# shiftReg.net
KiCad netlist of a schematic drawn in EAGLE
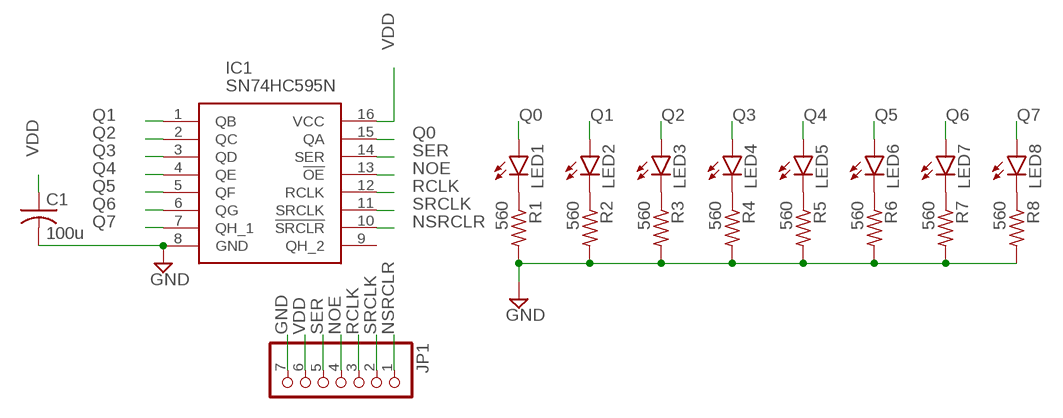
[diagram p0: schematic, sheet 1]

(export (version "E")
  (design (tool "Eeschema 10.0.6"))
  (components
    (comp (ref "C1")
      (value "100u")
      (footprint "eagle-import:C0805")
      (libsource (lib "eagle-import") (part "C-USC0805"))
    )
    (comp (ref "IC1")
      (value "SN74HC595N")
      (footprint "eagle-import:DIP794W53P254L1930H508Q16N")
      (fields (field (name "MOUSER_PART_NUMBER") "595-SN74HC595N"))
      (libsource (lib "eagle-import") (part "SN74HC595N"))
    )
    (comp (ref "JP1")
      (value "PINHD-1X7")
      (footprint "eagle-import:1X07")
      (libsource (lib "eagle-import") (part "PINHD-1X7"))
    )
    (comp (ref "LED1")
      (value "LEDCHIP-LED0805")
      (footprint "eagle-import:CHIP-LED0805")
      (libsource (lib "eagle-import") (part "LEDCHIP-LED0805"))
    )
    (comp (ref "LED2")
      (value "LEDCHIP-LED0805")
      (footprint "eagle-import:CHIP-LED0805")
      (libsource (lib "eagle-import") (part "LEDCHIP-LED0805"))
    )
    (comp (ref "LED3")
      (value "LEDCHIP-LED0805")
      (footprint "eagle-import:CHIP-LED0805")
      (libsource (lib "eagle-import") (part "LEDCHIP-LED0805"))
    )
    (comp (ref "LED4")
      (value "LEDCHIP-LED0805")
      (footprint "eagle-import:CHIP-LED0805")
      (libsource (lib "eagle-import") (part "LEDCHIP-LED0805"))
    )
    (comp (ref "LED5")
      (value "LEDCHIP-LED0805")
      (footprint "eagle-import:CHIP-LED0805")
      (libsource (lib "eagle-import") (part "LEDCHIP-LED0805"))
    )
    (comp (ref "LED6")
      (value "LEDCHIP-LED0805")
      (footprint "eagle-import:CHIP-LED0805")
      (libsource (lib "eagle-import") (part "LEDCHIP-LED0805"))
    )
    (comp (ref "LED7")
      (value "LEDCHIP-LED0805")
      (footprint "eagle-import:CHIP-LED0805")
      (libsource (lib "eagle-import") (part "LEDCHIP-LED0805"))
    )
    (comp (ref "LED8")
      (value "LEDCHIP-LED0805")
      (footprint "eagle-import:CHIP-LED0805")
      (libsource (lib "eagle-import") (part "LEDCHIP-LED0805"))
    )
    (comp (ref "R1")
      (value "560")
      (footprint "eagle-import:R0805")
      (libsource (lib "eagle-import") (part "R-US_R0805"))
    )
    (comp (ref "R2")
      (value "560")
      (footprint "eagle-import:R0805")
      (libsource (lib "eagle-import") (part "R-US_R0805"))
    )
    (comp (ref "R3")
      (value "560")
      (footprint "eagle-import:R0805")
      (libsource (lib "eagle-import") (part "R-US_R0805"))
    )
    (comp (ref "R4")
      (value "560")
      (footprint "eagle-import:R0805")
      (libsource (lib "eagle-import") (part "R-US_R0805"))
    )
    (comp (ref "R5")
      (value "560")
      (footprint "eagle-import:R0805")
      (libsource (lib "eagle-import") (part "R-US_R0805"))
    )
    (comp (ref "R6")
      (value "560")
      (footprint "eagle-import:R0805")
      (libsource (lib "eagle-import") (part "R-US_R0805"))
    )
    (comp (ref "R7")
      (value "560")
      (footprint "eagle-import:R0805")
      (libsource (lib "eagle-import") (part "R-US_R0805"))
    )
    (comp (ref "R8")
      (value "560")
      (footprint "eagle-import:R0805")
      (libsource (lib "eagle-import") (part "R-US_R0805"))
    )
  )
  (nets
    (net (code "1") (name "/NOE") (class "Default")
      (node (ref "IC1") (pin "13") (pinfunction "~{OE}_13") (pintype "bidirectional"))
      (node (ref "JP1") (pin "4") (pinfunction "4_4") (pintype "passive"))
    )
    (net (code "2") (name "/NSRCLR") (class "Default")
      (node (ref "IC1") (pin "10") (pinfunction "~{SRCLR}_10") (pintype "bidirectional"))
      (node (ref "JP1") (pin "1") (pinfunction "1_1") (pintype "passive"))
    )
    (net (code "3") (name "/Q0") (class "Default")
      (node (ref "IC1") (pin "15") (pinfunction "QA_15") (pintype "bidirectional"))
      (node (ref "LED1") (pin "A") (pinfunction "A_A") (pintype "passive"))
    )
    (net (code "4") (name "/Q1") (class "Default")
      (node (ref "IC1") (pin "1") (pinfunction "QB_1") (pintype "bidirectional"))
      (node (ref "LED2") (pin "A") (pinfunction "A_A") (pintype "passive"))
    )
    (net (code "5") (name "/Q2") (class "Default")
      (node (ref "IC1") (pin "2") (pinfunction "QC_2") (pintype "bidirectional"))
      (node (ref "LED3") (pin "A") (pinfunction "A_A") (pintype "passive"))
    )
    (net (code "6") (name "/Q3") (class "Default")
      (node (ref "IC1") (pin "3") (pinfunction "QD_3") (pintype "bidirectional"))
      (node (ref "LED4") (pin "A") (pinfunction "A_A") (pintype "passive"))
    )
    (net (code "7") (name "/Q4") (class "Default")
      (node (ref "IC1") (pin "4") (pinfunction "QE_4") (pintype "bidirectional"))
      (node (ref "LED5") (pin "A") (pinfunction "A_A") (pintype "passive"))
    )
    (net (code "8") (name "/Q5") (class "Default")
      (node (ref "IC1") (pin "5") (pinfunction "QF_5") (pintype "bidirectional"))
      (node (ref "LED6") (pin "A") (pinfunction "A_A") (pintype "passive"))
    )
    (net (code "9") (name "/Q6") (class "Default")
      (node (ref "IC1") (pin "6") (pinfunction "QG_6") (pintype "bidirectional"))
      (node (ref "LED7") (pin "A") (pinfunction "A_A") (pintype "passive"))
    )
    (net (code "10") (name "/Q7") (class "Default")
      (node (ref "IC1") (pin "7") (pinfunction "QH_1_7") (pintype "bidirectional"))
      (node (ref "LED8") (pin "A") (pinfunction "A_A") (pintype "passive"))
    )
    (net (code "11") (name "/RCLK") (class "Default")
      (node (ref "IC1") (pin "12") (pinfunction "RCLK_12") (pintype "input"))
      (node (ref "JP1") (pin "3") (pinfunction "3_3") (pintype "passive"))
    )
    (net (code "12") (name "/SER") (class "Default")
      (node (ref "IC1") (pin "14") (pinfunction "SER_14") (pintype "bidirectional"))
      (node (ref "JP1") (pin "5") (pinfunction "5_5") (pintype "passive"))
    )
    (net (code "13") (name "/SRCLK") (class "Default")
      (node (ref "IC1") (pin "11") (pinfunction "SRCLK_11") (pintype "input"))
      (node (ref "JP1") (pin "2") (pinfunction "2_2") (pintype "passive"))
    )
    (net (code "14") (name "/VDD") (class "Default")
      (node (ref "C1") (pin "1") (pinfunction "1_1") (pintype "passive"))
      (node (ref "IC1") (pin "16") (pinfunction "VCC_16") (pintype "power_in"))
      (node (ref "JP1") (pin "6") (pinfunction "6_6") (pintype "passive"))
    )
    (net (code "15") (name "GND") (class "Default")
      (node (ref "C1") (pin "2") (pinfunction "2_2") (pintype "passive"))
      (node (ref "IC1") (pin "8") (pinfunction "GND_8") (pintype "power_in"))
      (node (ref "JP1") (pin "7") (pinfunction "7_7") (pintype "passive"))
      (node (ref "R1") (pin "2") (pinfunction "2_2") (pintype "passive"))
      (node (ref "R2") (pin "2") (pinfunction "2_2") (pintype "passive"))
      (node (ref "R3") (pin "2") (pinfunction "2_2") (pintype "passive"))
      (node (ref "R4") (pin "2") (pinfunction "2_2") (pintype "passive"))
      (node (ref "R5") (pin "2") (pinfunction "2_2") (pintype "passive"))
      (node (ref "R6") (pin "2") (pinfunction "2_2") (pintype "passive"))
      (node (ref "R7") (pin "2") (pinfunction "2_2") (pintype "passive"))
      (node (ref "R8") (pin "2") (pinfunction "2_2") (pintype "passive"))
    )
    (net (code "16") (name "Net-(LED1-PadC)") (class "Default")
      (node (ref "LED1") (pin "C") (pinfunction "C_C") (pintype "passive"))
      (node (ref "R1") (pin "1") (pinfunction "1_1") (pintype "passive"))
    )
    (net (code "17") (name "Net-(LED2-PadC)") (class "Default")
      (node (ref "LED2") (pin "C") (pinfunction "C_C") (pintype "passive"))
      (node (ref "R2") (pin "1") (pinfunction "1_1") (pintype "passive"))
    )
    (net (code "18") (name "Net-(LED3-PadC)") (class "Default")
      (node (ref "LED3") (pin "C") (pinfunction "C_C") (pintype "passive"))
      (node (ref "R3") (pin "1") (pinfunction "1_1") (pintype "passive"))
    )
    (net (code "19") (name "Net-(LED4-PadC)") (class "Default")
      (node (ref "LED4") (pin "C") (pinfunction "C_C") (pintype "passive"))
      (node (ref "R4") (pin "1") (pinfunction "1_1") (pintype "passive"))
    )
    (net (code "20") (name "Net-(LED5-PadC)") (class "Default")
      (node (ref "LED5") (pin "C") (pinfunction "C_C") (pintype "passive"))
      (node (ref "R5") (pin "1") (pinfunction "1_1") (pintype "passive"))
    )
    (net (code "21") (name "Net-(LED6-PadC)") (class "Default")
      (node (ref "LED6") (pin "C") (pinfunction "C_C") (pintype "passive"))
      (node (ref "R6") (pin "1") (pinfunction "1_1") (pintype "passive"))
    )
    (net (code "22") (name "Net-(LED7-PadC)") (class "Default")
      (node (ref "LED7") (pin "C") (pinfunction "C_C") (pintype "passive"))
      (node (ref "R7") (pin "1") (pinfunction "1_1") (pintype "passive"))
    )
    (net (code "23") (name "Net-(LED8-PadC)") (class "Default")
      (node (ref "LED8") (pin "C") (pinfunction "C_C") (pintype "passive"))
      (node (ref "R8") (pin "1") (pinfunction "1_1") (pintype "passive"))
    )
    (net (code "24") (name "unconnected-(IC1-QH_2-Pad9)") (class "Default")
      (node (ref "IC1") (pin "9") (pinfunction "QH_2_9") (pintype "bidirectional"))
    )
  )
)
